# OpAmpDriver.net
KiCad netlist of a schematic drawn in EAGLE
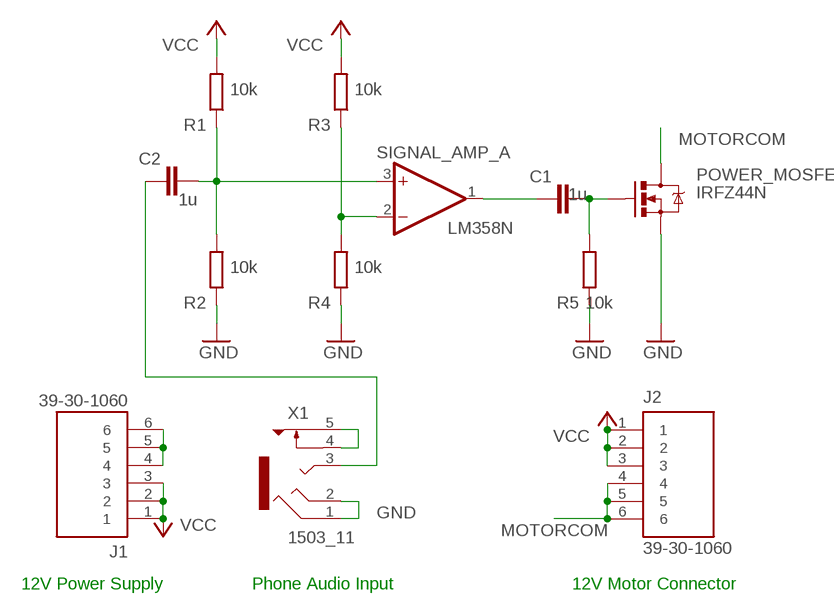
[diagram p0: schematic, sheet 1]

(export (version "E")
  (design (tool "Eeschema 10.0.6"))
  (components
    (comp (ref "C1")
      (value "1u")
      (footprint "eagle-import:C025-025X050")
      (libsource (lib "eagle-import") (part "C-EU025-025X050"))
    )
    (comp (ref "C2")
      (value "1u")
      (footprint "eagle-import:C025-025X050")
      (libsource (lib "eagle-import") (part "C-EU025-025X050"))
    )
    (comp (ref "J1")
      (value "39-30-1060")
      (footprint "eagle-import:MOLEX_39-30-1060")
      (fields (field (name "MF") "Molex"))
      (libsource (lib "eagle-import") (part "39-30-1060"))
    )
    (comp (ref "J2")
      (value "39-30-1060")
      (footprint "eagle-import:MOLEX_39-30-1060")
      (fields (field (name "MF") "Molex"))
      (libsource (lib "eagle-import") (part "39-30-1060"))
    )
    (comp (ref "POWER_MOSFET")
      (value "IRFZ44N")
      (footprint "eagle-import:TO-220")
      (fields (field (name "MF") "Infineon Technologies"))
      (libsource (lib "eagle-import") (part "IRFZ44N"))
    )
    (comp (ref "R1")
      (value "10k")
      (footprint "eagle-import:0204_7")
      (libsource (lib "eagle-import") (part "R-EU_0204/7"))
    )
    (comp (ref "R2")
      (value "10k")
      (footprint "eagle-import:0204_7")
      (libsource (lib "eagle-import") (part "R-EU_0204/7"))
    )
    (comp (ref "R3")
      (value "10k")
      (footprint "eagle-import:0204_7")
      (libsource (lib "eagle-import") (part "R-EU_0204/7"))
    )
    (comp (ref "R4")
      (value "10k")
      (footprint "eagle-import:0204_7")
      (libsource (lib "eagle-import") (part "R-EU_0204/7"))
    )
    (comp (ref "R5")
      (value "10k")
      (footprint "eagle-import:0204_7")
      (libsource (lib "eagle-import") (part "R-EU_0204/7"))
    )
    (comp (ref "SIGNAL_AMP_")
      (value "LM358N")
      (footprint "eagle-import:DIL08")
      (libsource (lib "eagle-import") (part "LM358N"))
    )
    (comp (ref "X1")
      (value "1503_11")
      (footprint "eagle-import:1503_11")
      (libsource (lib "eagle-import") (part "1503_11"))
    )
  )
  (nets
    (net (code "1") (name "/MOTORCOM") (class "Default")
      (node (ref "J2") (pin "4") (pinfunction "4_4") (pintype "passive"))
      (node (ref "J2") (pin "5") (pinfunction "5_5") (pintype "passive"))
      (node (ref "J2") (pin "6") (pinfunction "6_6") (pintype "passive"))
      (node (ref "POWER_MOSFET") (pin "2") (pinfunction "D_2") (pintype "passive"))
    )
    (net (code "2") (name "GND") (class "Default")
      (node (ref "POWER_MOSFET") (pin "3") (pinfunction "S_3") (pintype "passive"))
      (node (ref "R2") (pin "1") (pinfunction "1_1") (pintype "passive"))
      (node (ref "R4") (pin "1") (pinfunction "1_1") (pintype "passive"))
      (node (ref "R5") (pin "1") (pinfunction "1_1") (pintype "passive"))
      (node (ref "X1") (pin "1") (pinfunction "1_1") (pintype "passive"))
      (node (ref "X1") (pin "2") (pinfunction "2_2") (pintype "passive"))
    )
    (net (code "3") (name "Net-(C2-Pad1)") (class "Default")
      (node (ref "C2") (pin "1") (pinfunction "1_1") (pintype "passive"))
      (node (ref "X1") (pin "3") (pinfunction "3_3") (pintype "passive"))
    )
    (net (code "4") (name "Net-(J1-Pad4)") (class "Default")
      (node (ref "J1") (pin "4") (pinfunction "4_4") (pintype "passive"))
      (node (ref "J1") (pin "5") (pinfunction "5_5") (pintype "passive"))
      (node (ref "J1") (pin "6") (pinfunction "6_6") (pintype "passive"))
    )
    (net (code "5") (name "Net-(POWER_MOSFET-G)") (class "Default")
      (node (ref "C1") (pin "2") (pinfunction "2_2") (pintype "passive"))
      (node (ref "POWER_MOSFET") (pin "1") (pinfunction "G_1") (pintype "passive"))
      (node (ref "R5") (pin "2") (pinfunction "2_2") (pintype "passive"))
    )
    (net (code "6") (name "Net-(SIGNAL_AMP_A-+IN)") (class "Default")
      (node (ref "C2") (pin "2") (pinfunction "2_2") (pintype "passive"))
      (node (ref "R1") (pin "1") (pinfunction "1_1") (pintype "passive"))
      (node (ref "R2") (pin "2") (pinfunction "2_2") (pintype "passive"))
      (node (ref "SIGNAL_AMP_") (pin "3") (pinfunction "+IN_3") (pintype "input"))
    )
    (net (code "7") (name "Net-(SIGNAL_AMP_A--IN)") (class "Default")
      (node (ref "R3") (pin "1") (pinfunction "1_1") (pintype "passive"))
      (node (ref "R4") (pin "2") (pinfunction "2_2") (pintype "passive"))
      (node (ref "SIGNAL_AMP_") (pin "2") (pinfunction "-IN_2") (pintype "input"))
    )
    (net (code "8") (name "Net-(SIGNAL_AMP_A-OUT)") (class "Default")
      (node (ref "C1") (pin "1") (pinfunction "1_1") (pintype "passive"))
      (node (ref "SIGNAL_AMP_") (pin "1") (pinfunction "OUT_1") (pintype "output"))
    )
    (net (code "9") (name "Net-(X1-Pad4)") (class "Default")
      (node (ref "X1") (pin "4") (pinfunction "4_4") (pintype "passive"))
      (node (ref "X1") (pin "5") (pinfunction "5_5") (pintype "passive"))
    )
    (net (code "10") (name "VCC") (class "Default")
      (node (ref "J1") (pin "1") (pinfunction "1_1") (pintype "passive"))
      (node (ref "J1") (pin "2") (pinfunction "2_2") (pintype "passive"))
      (node (ref "J1") (pin "3") (pinfunction "3_3") (pintype "passive"))
      (node (ref "J2") (pin "1") (pinfunction "1_1") (pintype "passive"))
      (node (ref "J2") (pin "2") (pinfunction "2_2") (pintype "passive"))
      (node (ref "J2") (pin "3") (pinfunction "3_3") (pintype "passive"))
      (node (ref "R1") (pin "2") (pinfunction "2_2") (pintype "passive"))
      (node (ref "R3") (pin "2") (pinfunction "2_2") (pintype "passive"))
    )
  )
)
